# proximity_kt.net
KiCad netlist of a schematic drawn in Altium Designer
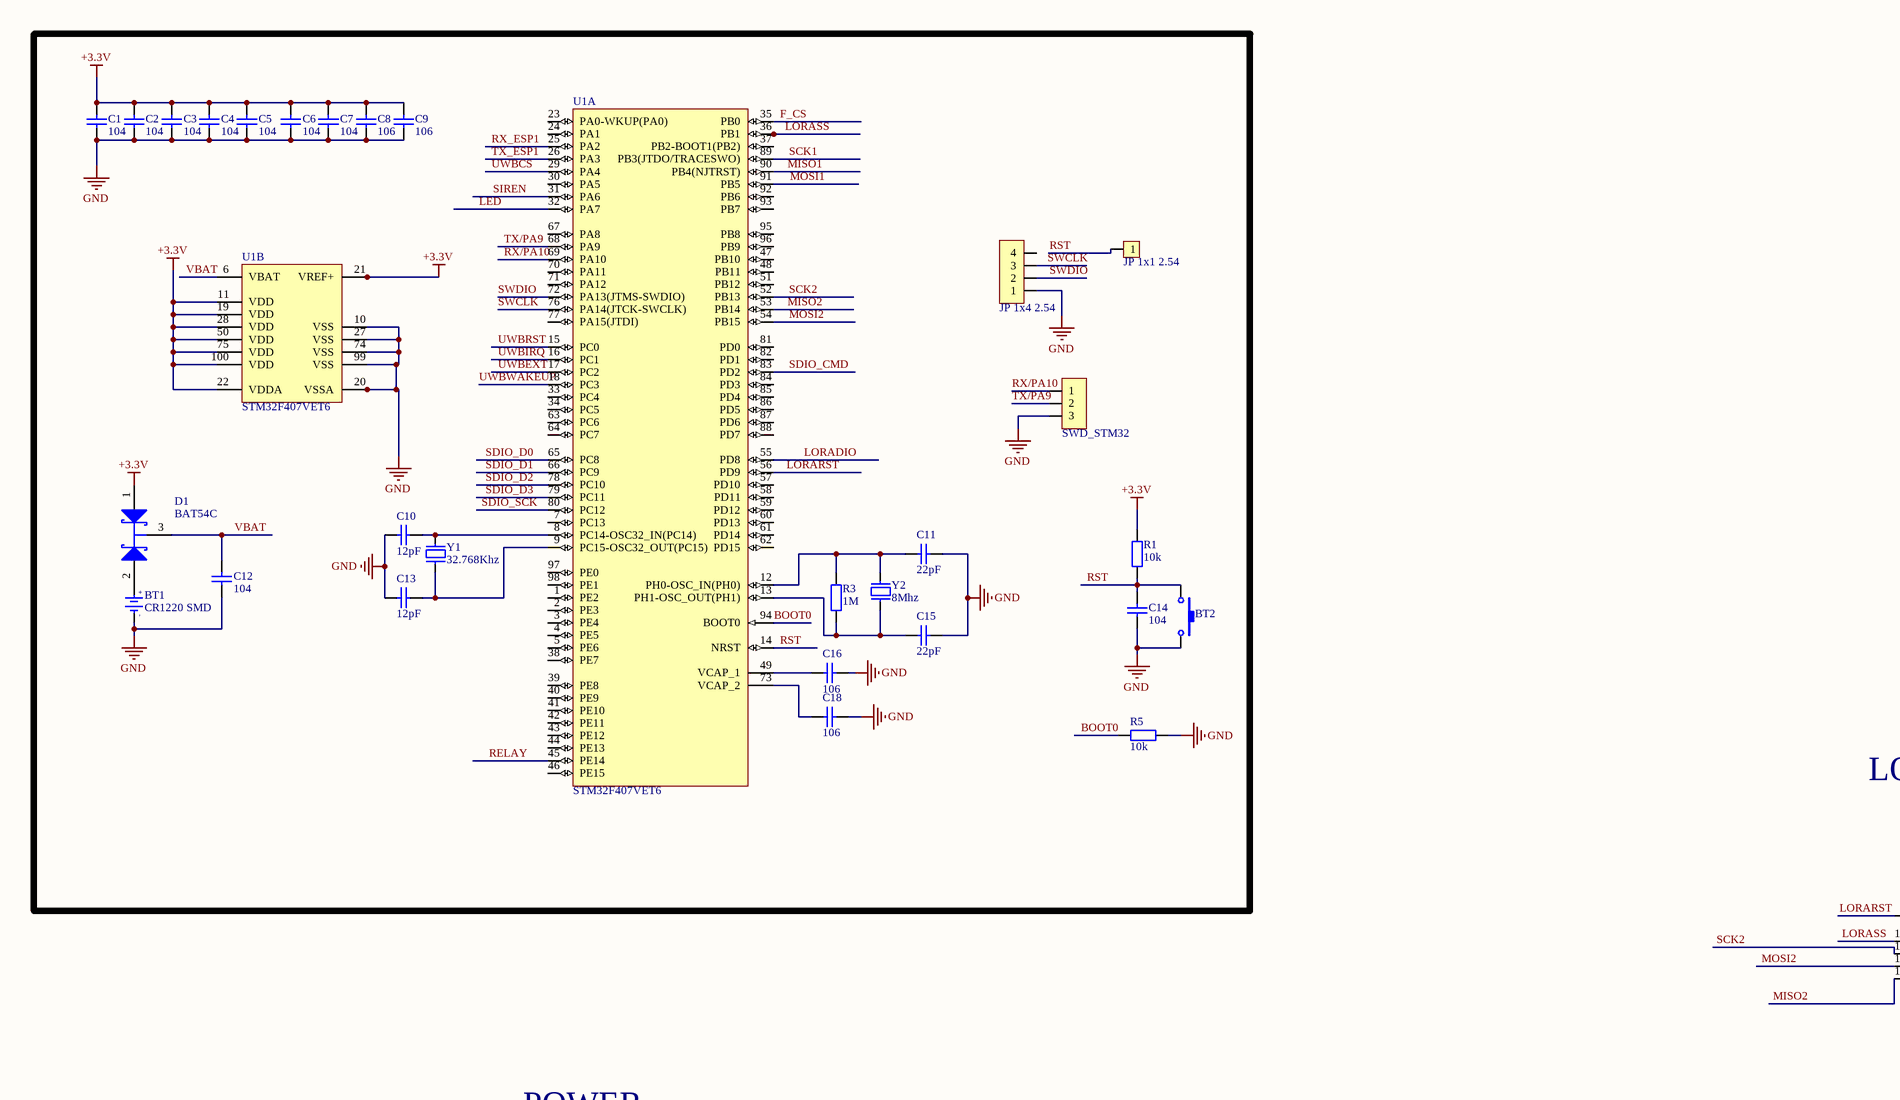
[diagram p0: proximity_kt.SchDoc, top left]
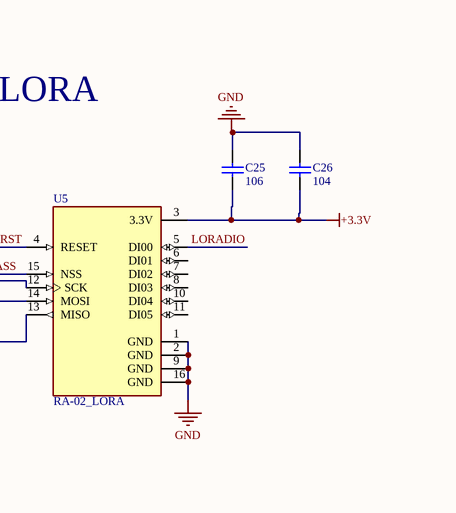
[diagram p1: proximity_kt.SchDoc, top right]
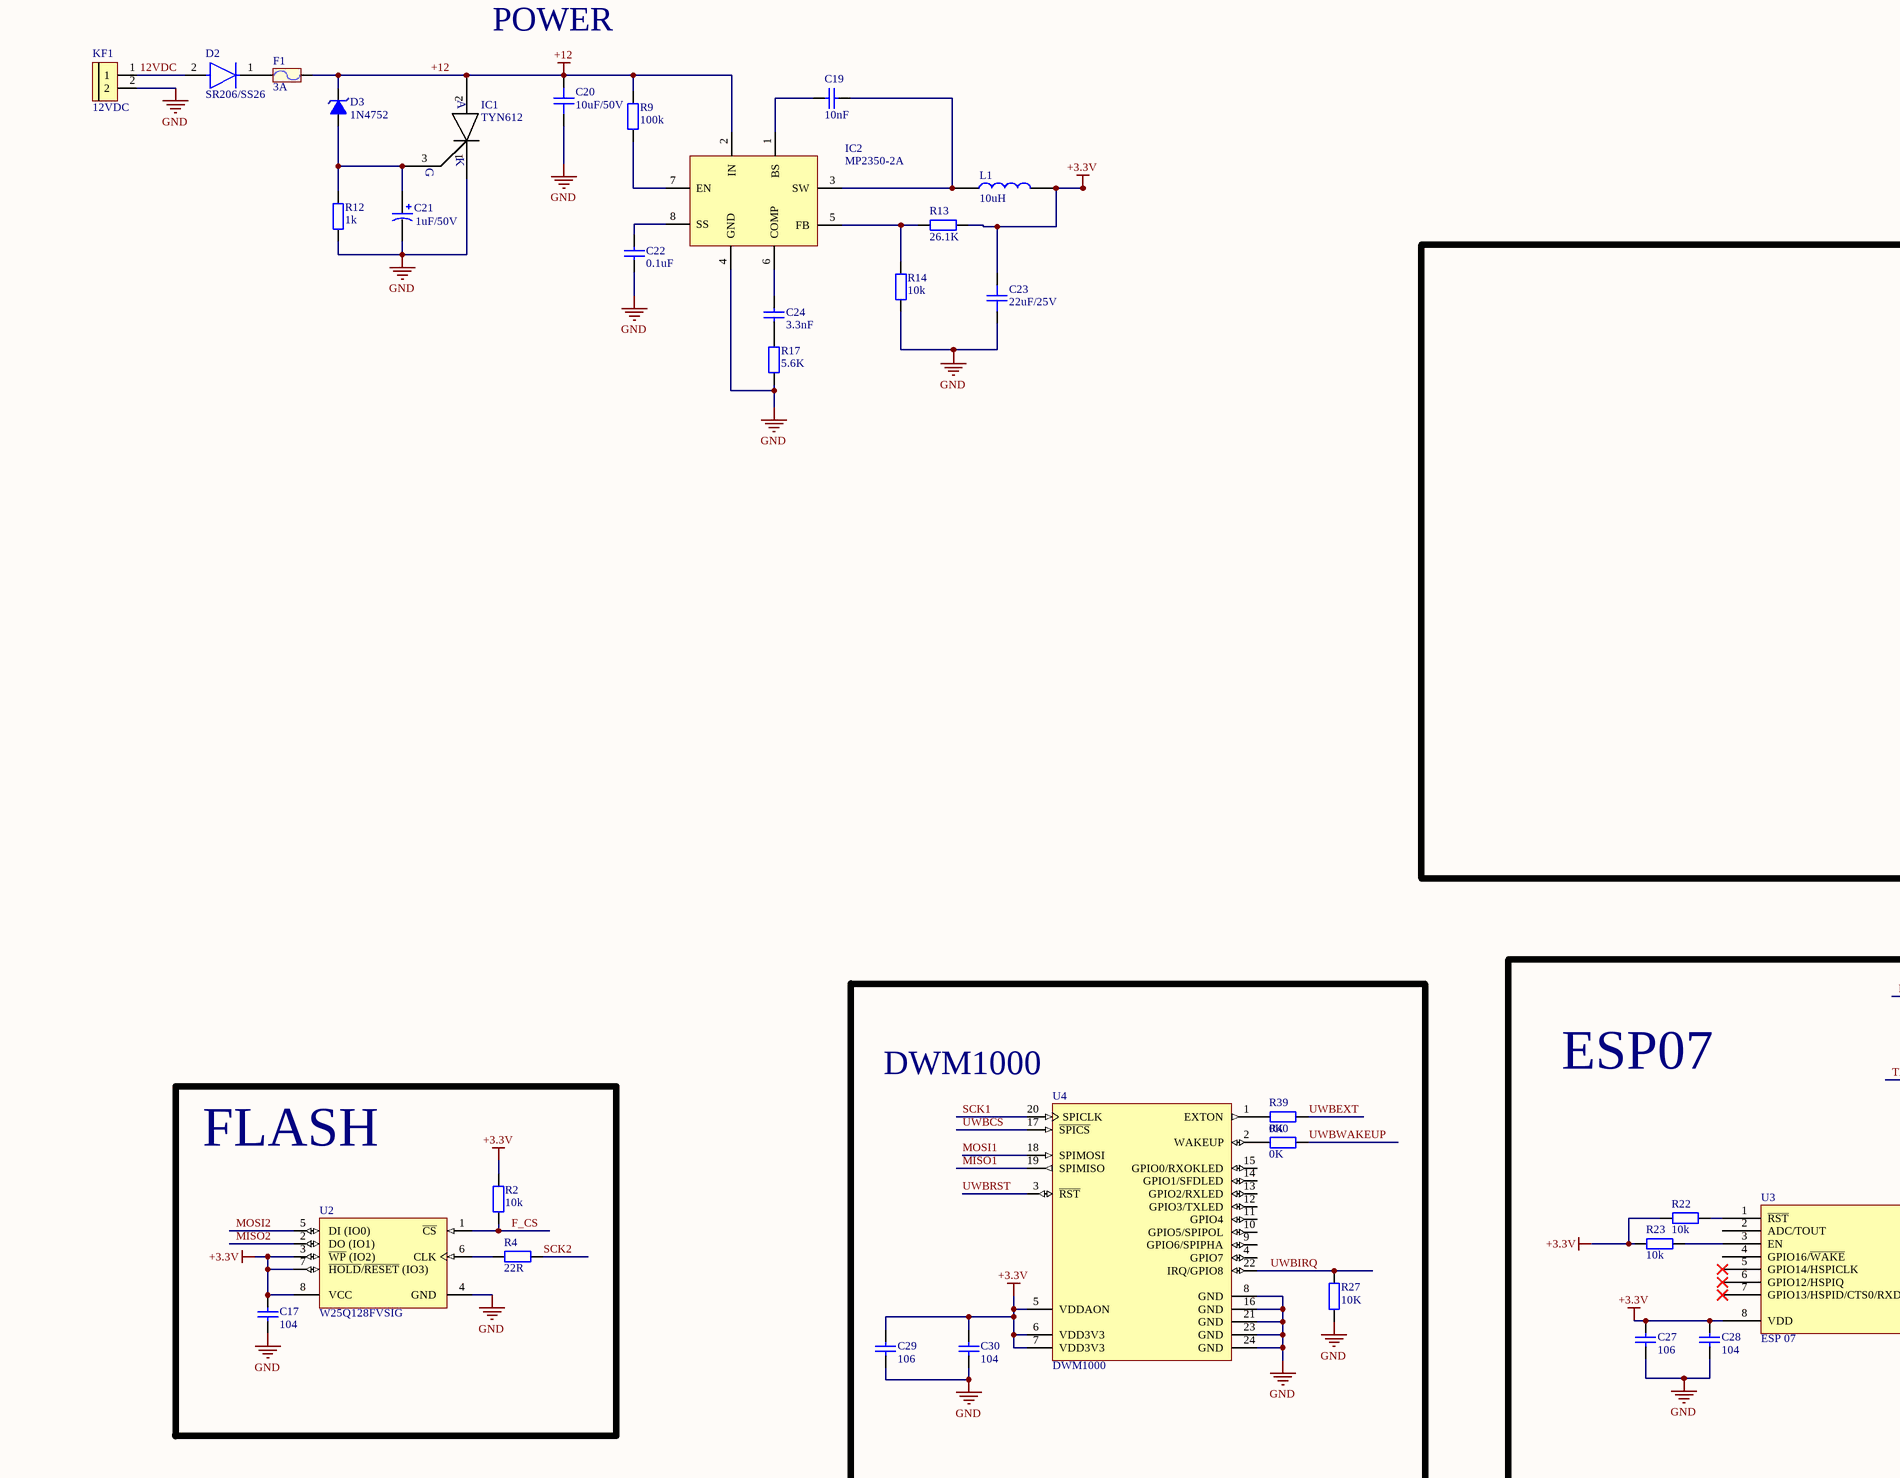
[diagram p2: proximity_kt.SchDoc, bottom left]
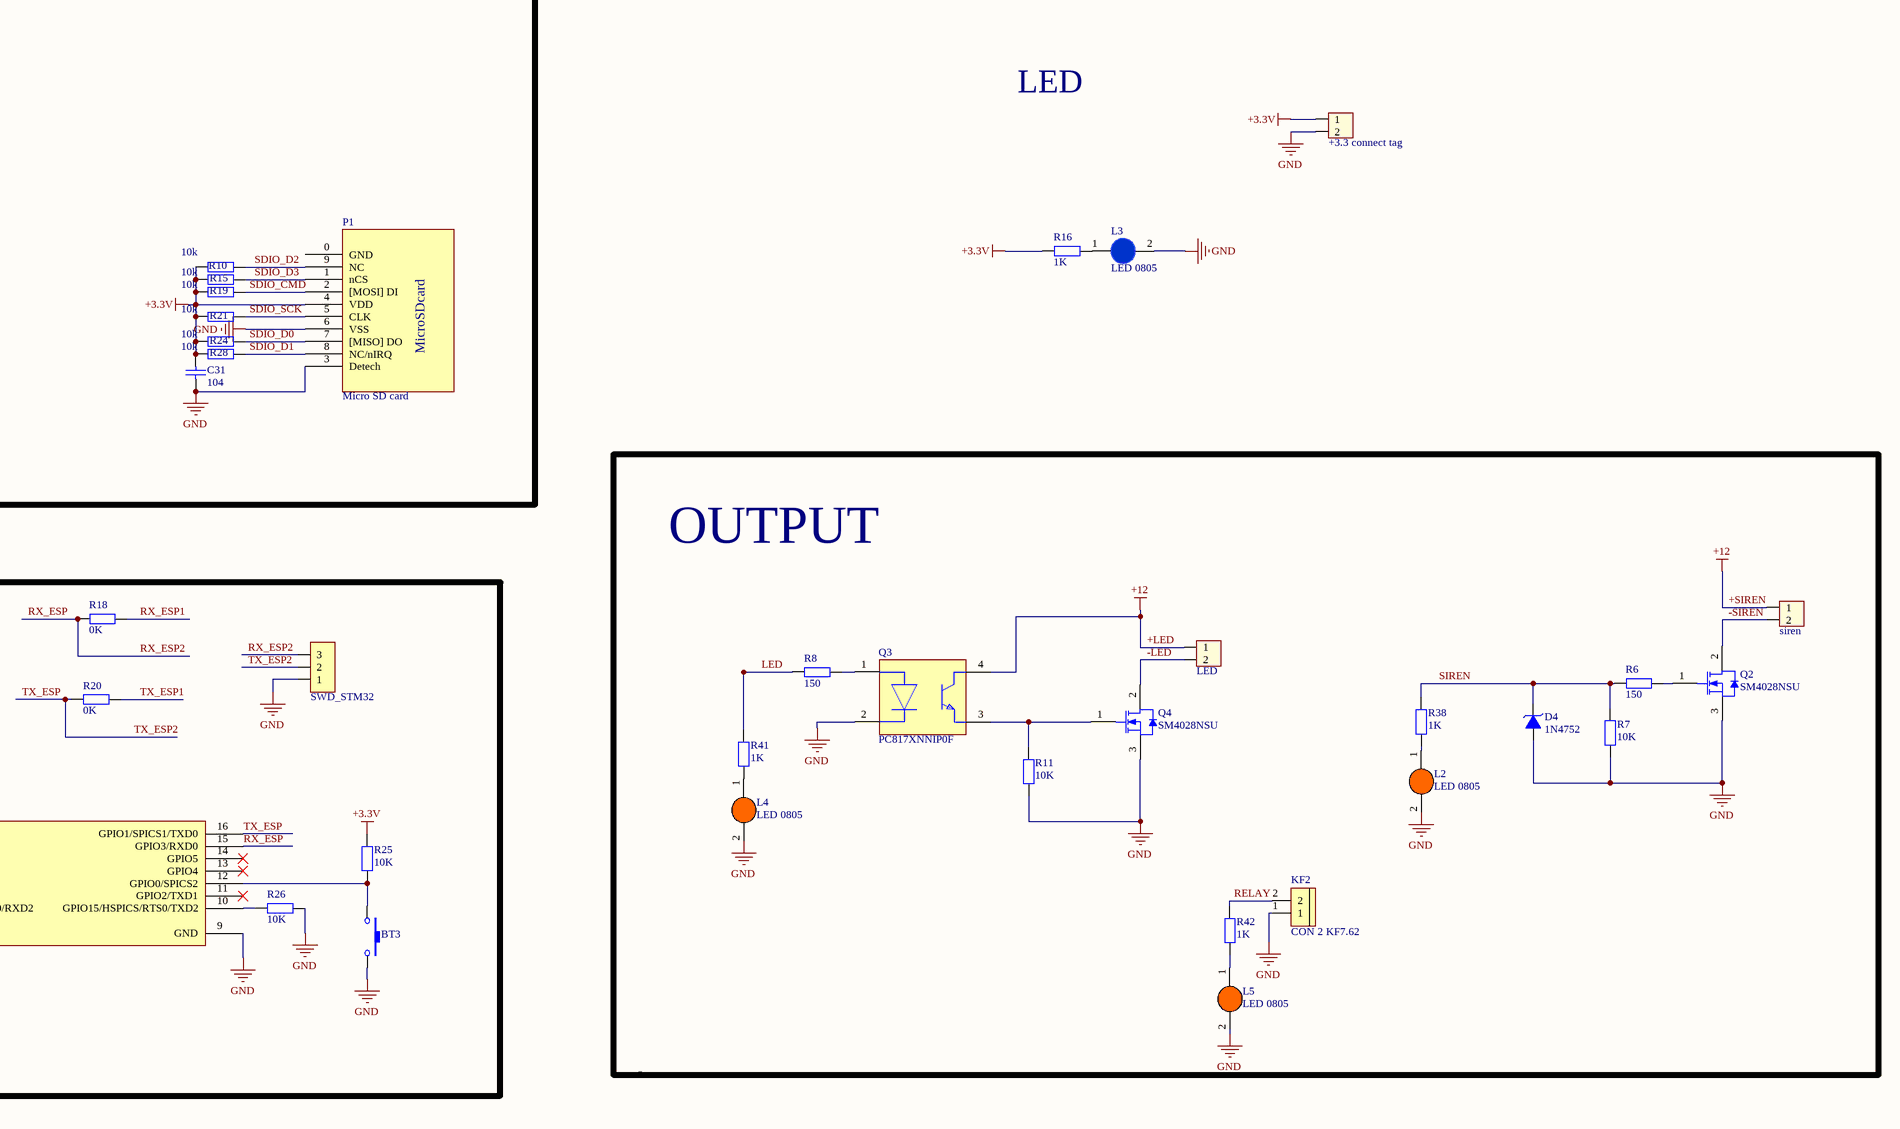
[diagram p3: proximity_kt.SchDoc, bottom right]

(export (version "E")
  (design (tool "Eeschema 10.0.6"))
  (components
    (comp (ref "BT1")
      (value "CR1220 SMD")
      (footprint "DE PIN CR1220")
      (libsource (lib "Altium_Lib_by_KhueNguyenCreator") (part "De pin CR1220 SMD"))
    )
    (comp (ref "BT2")
      (value "Nut Nhan 2 Chan SMD 3x6x2.5")
      (footprint "Nut Nhan 2 Chan SMD 3x6x2.5")
      (libsource (lib "Altium_Lib_by_KhueNguyenCreator") (part "Nut Nhan 2 Chan SMD 3x6x2.5"))
    )
    (comp (ref "BT3")
      (value "Nut Nhan 2 Chan SMD 3x6x2.5")
      (footprint "Nut Nhan 2 Chan SMD 3x6x2.5")
      (libsource (lib "Altium_Lib_by_KhueNguyenCreator") (part "Nut Nhan 2 Chan SMD 3x6x2.5"))
    )
    (comp (ref "C1")
      (value "104")
      (footprint "tu 0805")
      (description "Dán")
      (libsource (lib "Altium_Lib_by_KhueNguyenCreator") (part "Tu 0805 104 50V 10%"))
    )
    (comp (ref "C2")
      (value "104")
      (footprint "tu 0805")
      (description "Dán")
      (libsource (lib "Altium_Lib_by_KhueNguyenCreator") (part "Tu 0805 104 50V 10%"))
    )
    (comp (ref "C3")
      (value "104")
      (footprint "tu 0805")
      (description "Dán")
      (libsource (lib "Altium_Lib_by_KhueNguyenCreator") (part "Tu 0805 104 50V 10%"))
    )
    (comp (ref "C4")
      (value "104")
      (footprint "tu 0805")
      (description "Dán")
      (libsource (lib "Altium_Lib_by_KhueNguyenCreator") (part "Tu 0805 104 50V 10%"))
    )
    (comp (ref "C5")
      (value "104")
      (footprint "tu 0805")
      (description "Dán")
      (libsource (lib "Altium_Lib_by_KhueNguyenCreator") (part "Tu 0805 104 50V 10%"))
    )
    (comp (ref "C6")
      (value "104")
      (footprint "tu 0805")
      (description "Dán")
      (libsource (lib "Altium_Lib_by_KhueNguyenCreator") (part "Tu 0805 104 50V 10%"))
    )
    (comp (ref "C7")
      (value "104")
      (footprint "tu 0805")
      (description "Dán")
      (libsource (lib "Altium_Lib_by_KhueNguyenCreator") (part "Tu 0805 104 50V 10%"))
    )
    (comp (ref "C8")
      (value "106")
      (footprint "tu 0805")
      (description "Dán")
      (libsource (lib "Altium_Lib_by_KhueNguyenCreator") (part "Tu 0805 106 16V 10%"))
    )
    (comp (ref "C9")
      (value "106")
      (footprint "tu 0805")
      (description "Dán")
      (libsource (lib "Altium_Lib_by_KhueNguyenCreator") (part "Tu 0805 106 16V 10%"))
    )
    (comp (ref "C10")
      (value "12pF")
      (footprint "tu 0805")
      (description "Dán")
      (libsource (lib "Altium_Lib_by_KhueNguyenCreator") (part "Tu 0805 15pF 50V 10%"))
    )
    (comp (ref "C11")
      (value "22pF")
      (footprint "tu 0805")
      (description "Dán")
      (libsource (lib "Altium_Lib_by_KhueNguyenCreator") (part "Tu 0805 22pF 50V 10%"))
    )
    (comp (ref "C12")
      (value "104")
      (footprint "tu 0805")
      (description "Dán")
      (libsource (lib "Altium_Lib_by_KhueNguyenCreator") (part "Tu 0805 104 50V 10%"))
    )
    (comp (ref "C13")
      (value "12pF")
      (footprint "tu 0805")
      (description "Dán")
      (libsource (lib "Altium_Lib_by_KhueNguyenCreator") (part "Tu 0805 15pF 50V 10%"))
    )
    (comp (ref "C14")
      (value "104")
      (footprint "tu 0805")
      (description "Dán")
      (libsource (lib "Altium_Lib_by_KhueNguyenCreator") (part "Tu 0805 104 50V 10%"))
    )
    (comp (ref "C15")
      (value "22pF")
      (footprint "tu 0805")
      (description "Dán")
      (libsource (lib "Altium_Lib_by_KhueNguyenCreator") (part "Tu 0805 22pF 50V 10%"))
    )
    (comp (ref "C16")
      (value "106")
      (footprint "tu 0805")
      (description "Dán")
      (libsource (lib "Altium_Lib_by_KhueNguyenCreator") (part "Tu 0805 106 16V 10%"))
    )
    (comp (ref "C17")
      (value "104")
      (footprint "tu 0805")
      (description "Dán")
      (libsource (lib "Altium_Lib_by_KhueNguyenCreator") (part "Tu 0805 104 50V 10%"))
    )
    (comp (ref "C18")
      (value "106")
      (footprint "tu 0805")
      (description "Dán")
      (libsource (lib "Altium_Lib_by_KhueNguyenCreator") (part "Tu 0805 106 16V 10%"))
    )
    (comp (ref "C19")
      (value "10nF")
      (footprint "tu 0805")
      (description "Dán")
      (libsource (lib "Altium_Lib_by_KhueNguyenCreator") (part "Tu 0805 104 50V 10%"))
    )
    (comp (ref "C20")
      (value "10uF/50V")
      (footprint "CAPC-1210 (3225)")
      (description "CAP CER 220uF 20% 6.3V X5R 1210")
      (fields (field (name "MPN") "CL32A227MQVNNNE"))
      (libsource (lib "BYTECH_HW_LIB_2019 ") (part "CL32A227MQVNNNE"))
    )
    (comp (ref "C21")
      (value "1uF/50V")
      (footprint "CAP_ALUM_SMD_4054_TYPE_B")
      (description "CAP ALUM 10uF 20% 16V SMD")
      (fields (field (name "MPN") "EEE-HA1C100P") (field (name "MFR") "Panasonic"))
      (libsource (lib "BYTECH_HW_LIB_2019 ") (part "EEE-HA1C100P"))
    )
    (comp (ref "C22")
      (value "0.1uF")
      (footprint "tu 0805")
      (description "Dán")
      (libsource (lib "Altium_Lib_by_KhueNguyenCreator") (part "Tu 0805 104 50V 10%"))
    )
    (comp (ref "C23")
      (value "22uF/25V")
      (footprint "CAPC-1210 (3225)")
      (description "CAP CER 220uF 20% 6.3V X5R 1210")
      (fields (field (name "MPN") "CL32A227MQVNNNE"))
      (libsource (lib "BYTECH_HW_LIB_2019 ") (part "CL32A227MQVNNNE"))
    )
    (comp (ref "C24")
      (value "3.3nF")
      (footprint "tu 0805")
      (description "Dán")
      (libsource (lib "Altium_Lib_by_KhueNguyenCreator") (part "Tu 0805 104 50V 10%"))
    )
    (comp (ref "C25")
      (value "106")
      (footprint "tu 0805")
      (description "Dán")
      (libsource (lib "Altium_Lib_by_KhueNguyenCreator") (part "Tu 0805 106 16V 10%"))
    )
    (comp (ref "C26")
      (value "104")
      (footprint "tu 0805")
      (description "Dán")
      (libsource (lib "Altium_Lib_by_KhueNguyenCreator") (part "Tu 0805 104 50V 10%"))
    )
    (comp (ref "C27")
      (value "106")
      (footprint "tu 0805")
      (description "Dán")
      (libsource (lib "Altium_Lib_by_KhueNguyenCreator") (part "Tu 0805 106 16V 10%"))
    )
    (comp (ref "C28")
      (value "104")
      (footprint "tu 0805")
      (description "Dán")
      (libsource (lib "Altium_Lib_by_KhueNguyenCreator") (part "Tu 0805 104 50V 10%"))
    )
    (comp (ref "C29")
      (value "106")
      (footprint "tu 0805")
      (description "Dán")
      (libsource (lib "Altium_Lib_by_KhueNguyenCreator") (part "Tu 0805 106 16V 10%"))
    )
    (comp (ref "C30")
      (value "104")
      (footprint "tu 0805")
      (description "Dán")
      (libsource (lib "Altium_Lib_by_KhueNguyenCreator") (part "Tu 0805 104 50V 10%"))
    )
    (comp (ref "C31")
      (value "104")
      (footprint "tu 0805")
      (description "Dán")
      (libsource (lib "Altium_Lib_by_KhueNguyenCreator") (part "Tu 0805 104 50V 10%"))
    )
    (comp (ref "D1")
      (value "BAT54C")
      (footprint "NXP-SOT23-3_V")
      (description "Schottky Barrier Diode, 30 V, 2 uA, -55 to 150 degC, 3-Pin SOT23, RoHS, Tape and Reel")
      (fields (field (name "MANUFACTURER") "NXP Semiconductors"))
      (libsource (lib "Altium Content Vault") (part "NXP-DSKY_A1A2K3-3"))
    )
    (comp (ref "D2")
      (value "SR206/SS26")
      (footprint "FP-95401-MFG")
      (description "DIODE GEN PURP 600V 2A DO214AA")
      (libsource (lib "Altium Content Vault") (part "d7152d700b627762746794eb795d46e"))
    )
    (comp (ref "D3")
      (value "1N4752")
      (footprint "DIODE ZENNER SMD SOD80")
      (description "Dán")
      (libsource (lib "Altium_Lib_by_KhueNguyenCreator") (part "Diode Zener 15V"))
    )
    (comp (ref "D4")
      (value "1N4752")
      (footprint "DIODE ZENNER SMD SOD80")
      (description "Dán")
      (libsource (lib "Altium_Lib_by_KhueNguyenCreator") (part "Diode Zener 15V"))
    )
    (comp (ref "F1")
      (value "3A")
      (footprint "Cau Chi SMD1808")
      (description "Cau chi 0.5A 125V SMD1808")
      (libsource (lib "Altium_Lib_by_KhueNguyenCreator") (part "Cau chi 0.5A 125V SMD1808"))
    )
    (comp (ref "H2")
      (value "siren")
      (footprint "XH2.54M-2")
      (description "Cắm")
      (libsource (lib "Altium_Lib_by_KhueNguyenCreator") (part "Header 2P 2.54 Duc Thang"))
    )
    (comp (ref "H3")
      (value "+3.3 connect tag")
      (footprint "XH2.54M-2")
      (description "Cắm")
      (libsource (lib "Altium_Lib_by_KhueNguyenCreator") (part "Header 2P 2.54 Duc Thang"))
    )
    (comp (ref "H5")
      (value "LED")
      (footprint "XH2.54M-2")
      (description "Cắm")
      (libsource (lib "Altium_Lib_by_KhueNguyenCreator") (part "Header 2P 2.54 Duc Thang"))
    )
    (comp (ref "IC1")
      (value "TYN612")
      (footprint "TYN612VER1")
      (libsource (lib "Integrated_Library1") (part "TYN612"))
    )
    (comp (ref "IC2")
      (value "MP2350-2A")
      (footprint "MP2305")
      (libsource (lib "Integrated_Library1") (part "MP2350-2A"))
    )
    (comp (ref "JP1")
      (value "JP 1x4 2.54")
      (footprint "JP 1x4 DT")
      (description "Cắm")
      (libsource (lib "Altium_Lib_by_KhueNguyenCreator") (part "JP 1x4 2.54 Duc Thang"))
    )
    (comp (ref "JP2")
      (value "SWD_STM32")
      (footprint "JP 1x3 DT")
      (description "Cắm")
      (libsource (lib "Altium_Lib_by_KhueNguyenCreator") (part "JP 1x3 2.54 Duc Thang"))
    )
    (comp (ref "JP3")
      (value "SWD_STM32")
      (footprint "JP 1x3 DT")
      (description "Cắm")
      (libsource (lib "") (part "JP 1x3 2.54 Duc Thang_1"))
    )
    (comp (ref "JP5")
      (value "JP 1x1 2.54")
      (footprint "JP 1x1 DT")
      (description "Cắm")
      (libsource (lib "Altium_Lib_by_KhueNguyenCreator") (part "JP 1x1 2.54 Duc Thang"))
    )
    (comp (ref "KF1")
      (value "12VDC")
      (footprint "Con 2 KF301 5.08")
      (description "Cắm")
      (libsource (lib "Altium_Lib_by_KhueNguyenCreator") (part "CON 2 KF301"))
    )
    (comp (ref "KF2")
      (value "CON 2 KF7.62")
      (footprint "CON 2 KF7.62")
      (description "Cắm")
      (libsource (lib "Altium_Lib_by_KhueNguyenCreator") (part "CON 2 KF7.62"))
    )
    (comp (ref "L1")
      (value "10uH")
      (footprint "Cuon Cam 7x7x5")
      (description "Dán")
      (libsource (lib "Altium_Lib_by_KhueNguyenCreator") (part "CUON CAM 47uH SMD"))
    )
    (comp (ref "L2")
      (value "LED 0805")
      (footprint "LED-0805-Orange")
      (description "Dán")
      (libsource (lib "Altium_Lib_by_KhueNguyenCreator") (part "LED 0805 Cam"))
    )
    (comp (ref "L3")
      (value "LED 0805")
      (footprint "LED-0805-Blue")
      (description "Dán")
      (libsource (lib "Altium_Lib_by_KhueNguyenCreator") (part "LED 0805 Xanh Duong"))
    )
    (comp (ref "L4")
      (value "LED 0805")
      (footprint "LED-0805-Orange")
      (description "Dán")
      (libsource (lib "Altium_Lib_by_KhueNguyenCreator") (part "LED 0805 Cam"))
    )
    (comp (ref "L5")
      (value "LED 0805")
      (footprint "LED-0805-Orange")
      (description "Dán")
      (libsource (lib "Altium_Lib_by_KhueNguyenCreator") (part "LED 0805 Cam"))
    )
    (comp (ref "P1")
      (value "Micro SD card")
      (footprint "MicroSD")
      (libsource (lib "Altium_Lib_by_KhueNguyenCreator") (part "Micro SD card"))
    )
    (comp (ref "Q2")
      (value "SM4028NSU")
      (footprint "INF-PG-TO252-3-313_L")
      (fields (field (name "MANUFACTURER") "Infineon") (field (name "PARTNUMBER") "IPD60R600C6"))
      (libsource (lib "Altium Content Vault") (part "INF-NEMOS-GDS-3"))
    )
    (comp (ref "Q3")
      (value "PC817XNNIP0F")
      (footprint "FP-PC817XNNIP0F-MFG")
      (description "OPTOISOLATOR 5KV TRANS 4SMD")
      (libsource (lib "Altium Content Vault") (part "6470904bf6395c62928ee73e60120b8"))
    )
    (comp (ref "Q4")
      (value "SM4028NSU")
      (footprint "INF-PG-TO252-3-313_L")
      (fields (field (name "MANUFACTURER") "Infineon") (field (name "PARTNUMBER") "IPD60R600C6"))
      (libsource (lib "Altium Content Vault") (part "INF-NEMOS-GDS-3"))
    )
    (comp (ref "R1")
      (value "10k")
      (footprint "tro smd 0805")
      (description "Dán")
      (libsource (lib "Altium_Lib_by_KhueNguyenCreator") (part "Tro 0805 5% 10k"))
    )
    (comp (ref "R2")
      (value "10k")
      (footprint "tro smd 0805")
      (description "Dán")
      (libsource (lib "Altium_Lib_by_KhueNguyenCreator") (part "Tro 0805 5% 10k"))
    )
    (comp (ref "R3")
      (value "1M")
      (footprint "tro smd 0805")
      (description "Dán")
      (libsource (lib "Altium_Lib_by_KhueNguyenCreator") (part "Tro 0805 1% 1M"))
    )
    (comp (ref "R4")
      (value "22R")
      (footprint "tro smd 0805")
      (description "Dán")
      (libsource (lib "Altium_Lib_by_KhueNguyenCreator") (part "Tro 0805 1% 0.22R"))
    )
    (comp (ref "R5")
      (value "10k")
      (footprint "tro smd 0805")
      (description "Dán")
      (libsource (lib "Altium_Lib_by_KhueNguyenCreator") (part "Tro 0805 5% 10k"))
    )
    (comp (ref "R6")
      (value "150")
      (footprint "tro smd 0805")
      (description "Dán")
      (libsource (lib "Altium_Lib_by_KhueNguyenCreator") (part "Tro 0603 5% 10k"))
    )
    (comp (ref "R7")
      (value "10K")
      (footprint "tro smd 0805")
      (description "Dán")
      (libsource (lib "Altium_Lib_by_KhueNguyenCreator") (part "Tro 0603 5% 10k"))
    )
    (comp (ref "R8")
      (value "150")
      (footprint "tro smd 0805")
      (description "Dán")
      (libsource (lib "Altium_Lib_by_KhueNguyenCreator") (part "Tro 0603 5% 10k"))
    )
    (comp (ref "R9")
      (value "100k")
      (footprint "tro smd 0805")
      (description "Dán")
      (libsource (lib "Altium_Lib_by_KhueNguyenCreator") (part "Tro 0805 5% 10k"))
    )
    (comp (ref "R10")
      (value "10k")
      (footprint "tro smd 0805")
      (description "Dán")
      (libsource (lib "Altium_Lib_by_KhueNguyenCreator") (part "Tro 0805 5% 10k"))
    )
    (comp (ref "R11")
      (value "10K")
      (footprint "tro smd 0805")
      (description "Dán")
      (libsource (lib "Altium_Lib_by_KhueNguyenCreator") (part "Tro 0603 5% 10k"))
    )
    (comp (ref "R12")
      (value "1k")
      (footprint "tro smd 0805")
      (description "Dán")
      (libsource (lib "Altium_Lib_by_KhueNguyenCreator") (part "Tro 0805 1% 1k"))
    )
    (comp (ref "R13")
      (value "26.1K")
      (footprint "tro smd 0805")
      (description "Dán")
      (libsource (lib "Altium_Lib_by_KhueNguyenCreator") (part "Tro 0805 5% 10k"))
    )
    (comp (ref "R14")
      (value "10k")
      (footprint "tro smd 0805")
      (description "Dán")
      (libsource (lib "Altium_Lib_by_KhueNguyenCreator") (part "Tro 0805 5% 10k"))
    )
    (comp (ref "R15")
      (value "10k")
      (footprint "tro smd 0805")
      (description "Dán")
      (libsource (lib "Altium_Lib_by_KhueNguyenCreator") (part "Tro 0805 5% 10k"))
    )
    (comp (ref "R16")
      (value "1K")
      (footprint "tro smd 0805")
      (description "Dán")
      (libsource (lib "Altium_Lib_by_KhueNguyenCreator") (part "Tro 0603 5% 10k"))
    )
    (comp (ref "R17")
      (value "5.6K")
      (footprint "tro smd 0805")
      (description "Dán")
      (libsource (lib "Altium_Lib_by_KhueNguyenCreator") (part "Tro 0805 5% 10k"))
    )
    (comp (ref "R18")
      (value "0K")
      (footprint "tro smd 0805")
      (description "Dán")
      (libsource (lib "Altium_Lib_by_KhueNguyenCreator") (part "Tro 0603 5% 10k"))
    )
    (comp (ref "R19")
      (value "10k")
      (footprint "tro smd 0805")
      (description "Dán")
      (libsource (lib "Altium_Lib_by_KhueNguyenCreator") (part "Tro 0805 5% 10k"))
    )
    (comp (ref "R20")
      (value "0K")
      (footprint "tro smd 0805")
      (description "Dán")
      (libsource (lib "Altium_Lib_by_KhueNguyenCreator") (part "Tro 0603 5% 10k"))
    )
    (comp (ref "R21")
      (value "10k")
      (footprint "tro smd 0805")
      (description "Dán")
      (libsource (lib "Altium_Lib_by_KhueNguyenCreator") (part "Tro 0805 5% 10k"))
    )
    (comp (ref "R22")
      (value "10k")
      (footprint "tro smd 0805")
      (description "Dán")
      (libsource (lib "Altium_Lib_by_KhueNguyenCreator") (part "Tro 0805 5% 10k"))
    )
    (comp (ref "R23")
      (value "10k")
      (footprint "tro smd 0805")
      (description "Dán")
      (libsource (lib "Altium_Lib_by_KhueNguyenCreator") (part "Tro 0805 5% 10k"))
    )
    (comp (ref "R24")
      (value "10k")
      (footprint "tro smd 0805")
      (description "Dán")
      (libsource (lib "Altium_Lib_by_KhueNguyenCreator") (part "Tro 0805 5% 10k"))
    )
    (comp (ref "R25")
      (value "10K")
      (footprint "tro smd 0805")
      (description "Dán")
      (libsource (lib "Altium_Lib_by_KhueNguyenCreator") (part "Tro 0603 5% 10k"))
    )
    (comp (ref "R26")
      (value "10K")
      (footprint "tro smd 0805")
      (description "Dán")
      (libsource (lib "Altium_Lib_by_KhueNguyenCreator") (part "Tro 0603 5% 10k"))
    )
    (comp (ref "R27")
      (value "10K")
      (footprint "tro smd 0805")
      (description "Dán")
      (libsource (lib "Altium_Lib_by_KhueNguyenCreator") (part "Tro 0603 5% 10k"))
    )
    (comp (ref "R28")
      (value "10k")
      (footprint "tro smd 0805")
      (description "Dán")
      (libsource (lib "Altium_Lib_by_KhueNguyenCreator") (part "Tro 0805 5% 10k"))
    )
    (comp (ref "R38")
      (value "1K")
      (footprint "tro smd 0805")
      (description "Dán")
      (libsource (lib "Altium_Lib_by_KhueNguyenCreator") (part "Tro 0603 5% 10k"))
    )
    (comp (ref "R39")
      (value "0K")
      (footprint "tro smd 0805")
      (description "Dán")
      (libsource (lib "Altium_Lib_by_KhueNguyenCreator") (part "Tro 0603 5% 10k"))
    )
    (comp (ref "R40")
      (value "0K")
      (footprint "tro smd 0805")
      (description "Dán")
      (libsource (lib "Altium_Lib_by_KhueNguyenCreator") (part "Tro 0603 5% 10k"))
    )
    (comp (ref "R41")
      (value "1K")
      (footprint "tro smd 0805")
      (description "Dán")
      (libsource (lib "Altium_Lib_by_KhueNguyenCreator") (part "Tro 0603 5% 10k"))
    )
    (comp (ref "R42")
      (value "1K")
      (footprint "tro smd 0805")
      (description "Dán")
      (libsource (lib "Altium_Lib_by_KhueNguyenCreator") (part "Tro 0603 5% 10k"))
    )
    (comp (ref "U1")
      (value "STM32F407VET6")
      (footprint "STM-LQFP100_M")
      (fields (field (name "MANUFACTURER") "STMicroelectronics"))
      (libsource (lib "Altium Content Vault") (part "MC-ARM-STM32F40X_41X-SQ100"))
    )
    (comp (ref "U2")
      (value "W25Q128FVSIG")
      (footprint "WINB-SOIC-8_M")
      (fields (field (name "MANUFACTURER") "Winbond"))
      (libsource (lib "Altium Content Vault") (part "WINB-W25Q128FVSIG-SOIC-8"))
    )
    (comp (ref "U3")
      (value "ESP 07")
      (footprint "ESP8266 07")
      (description "ESP8266 07 16 Pin")
      (libsource (lib "Altium_Lib_by_KhueNguyenCreator") (part "ESP8266 07"))
    )
    (comp (ref "U4")
      (value "DWM1000")
      (footprint "DECW-DWM1000-24_V")
      (description "DW M1000 IEEE 802.15.4 -2011 UWB Transceiver Module")
      (fields (field (name "MANUFACTURER") "Decawave"))
      (libsource (lib "Altium Content Vault") (part "DECW-DWM1000-24"))
    )
    (comp (ref "U5")
      (value "RA-02_LORA")
      (footprint "MODULE_RA-02_LORA")
      (description "Ra-02 LoRa RF M5Stack Platform Evaluation Expansion Board")
      (fields (field (name "MP") "Ra-02 LoRa") (field (name "MF") "AI-Thinker"))
      (libsource (lib "Integrated_Library1") (part "RA-02_LORA"))
    )
    (comp (ref "Y1")
      (value "32.768Khz")
      (footprint "Thach Anh 2 Chan 32,768 KHz")
      (description "Crystal For all Crystal 2pin.")
      (libsource (lib "Altium_Lib_by_KhueNguyenCreator") (part "Thach Anh 2 chan 32,768 Khz"))
    )
    (comp (ref "Y2")
      (value "8Mhz")
      (footprint "Thach Anh 2 chan SMD")
      (description "Crystal For all Crystal 2pin.")
      (libsource (lib "Altium_Lib_by_KhueNguyenCreator") (part "Thach Anh 2 chan SMD"))
    )
  )
  (nets
    (net (code "1") (name "+3.3V") (class "Default")
      (node (ref "C1") (pin "1") (pinfunction "1_1") (pintype "passive"))
      (node (ref "C17") (pin "1") (pinfunction "1_1") (pintype "passive"))
      (node (ref "C2") (pin "1") (pinfunction "1_1") (pintype "passive"))
      (node (ref "C23") (pin "2") (pinfunction "2_2") (pintype "passive"))
      (node (ref "C25") (pin "2") (pinfunction "2_2") (pintype "passive"))
      (node (ref "C26") (pin "2") (pinfunction "2_2") (pintype "passive"))
      (node (ref "C27") (pin "1") (pinfunction "1_1") (pintype "passive"))
      (node (ref "C28") (pin "1") (pinfunction "1_1") (pintype "passive"))
      (node (ref "C29") (pin "1") (pinfunction "1_1") (pintype "passive"))
      (node (ref "C3") (pin "1") (pinfunction "1_1") (pintype "passive"))
      (node (ref "C30") (pin "1") (pinfunction "1_1") (pintype "passive"))
      (node (ref "C31") (pin "1") (pinfunction "1_1") (pintype "passive"))
      (node (ref "C4") (pin "1") (pinfunction "1_1") (pintype "passive"))
      (node (ref "C5") (pin "1") (pinfunction "1_1") (pintype "passive"))
      (node (ref "C6") (pin "1") (pinfunction "1_1") (pintype "passive"))
      (node (ref "C7") (pin "1") (pinfunction "1_1") (pintype "passive"))
      (node (ref "C8") (pin "1") (pinfunction "1_1") (pintype "passive"))
      (node (ref "C9") (pin "1") (pinfunction "1_1") (pintype "passive"))
      (node (ref "D1") (pin "1") (pinfunction "A_1") (pintype "passive"))
      (node (ref "H3") (pin "1") (pinfunction "1_1") (pintype "passive"))
      (node (ref "L1") (pin "2") (pinfunction "2_2") (pintype "passive"))
      (node (ref "P1") (pin "4") (pinfunction "VDD_4") (pintype "passive"))
      (node (ref "R1") (pin "2") (pinfunction "2_2") (pintype "passive"))
      (node (ref "R10") (pin "2") (pinfunction "2_2") (pintype "passive"))
      (node (ref "R13") (pin "2") (pinfunction "2_2") (pintype "passive"))
      (node (ref "R15") (pin "2") (pinfunction "2_2") (pintype "passive"))
      (node (ref "R16") (pin "2") (pinfunction "2_2") (pintype "passive"))
      (node (ref "R19") (pin "2") (pinfunction "2_2") (pintype "passive"))
      (node (ref "R2") (pin "2") (pinfunction "2_2") (pintype "passive"))
      (node (ref "R21") (pin "2") (pinfunction "2_2") (pintype "passive"))
      (node (ref "R22") (pin "2") (pinfunction "2_2") (pintype "passive"))
      (node (ref "R23") (pin "2") (pinfunction "2_2") (pintype "passive"))
      (node (ref "R24") (pin "2") (pinfunction "2_2") (pintype "passive"))
      (node (ref "R25") (pin "2") (pinfunction "2_2") (pintype "passive"))
      (node (ref "R28") (pin "2") (pinfunction "2_2") (pintype "passive"))
      (node (ref "U1") (pin "100") (pinfunction "VDD_100") (pintype "power_in"))
      (node (ref "U1") (pin "11") (pinfunction "VDD_11") (pintype "power_in"))
      (node (ref "U1") (pin "19") (pinfunction "VDD_19") (pintype "power_in"))
      (node (ref "U1") (pin "21") (pinfunction "VREF+_21") (pintype "power_in"))
      (node (ref "U1") (pin "22") (pinfunction "VDDA_22") (pintype "power_in"))
      (node (ref "U1") (pin "28") (pinfunction "VDD_28") (pintype "power_in"))
      (node (ref "U1") (pin "50") (pinfunction "VDD_50") (pintype "power_in"))
      (node (ref "U1") (pin "75") (pinfunction "VDD_75") (pintype "power_in"))
      (node (ref "U2") (pin "3") (pinfunction "~{WP}_(IO2)_3") (pintype "bidirectional"))
      (node (ref "U2") (pin "7") (pinfunction "~{HOLD}/~{RESET}_(IO3)_7") (pintype "bidirectional"))
      (node (ref "U2") (pin "8") (pinfunction "VCC_8") (pintype "power_in"))
      (node (ref "U3") (pin "8") (pinfunction "VDD_8") (pintype "passive"))
      (node (ref "U4") (pin "5") (pinfunction "VDDAON_5") (pintype "power_in"))
      (node (ref "U4") (pin "6") (pinfunction "VDD3V3_6") (pintype "power_in"))
      (node (ref "U4") (pin "7") (pinfunction "VDD3V3_7") (pintype "power_in"))
      (node (ref "U5") (pin "3") (pinfunction "3.3V_3") (pintype "power_in"))
    )
    (net (code "2") (name "+12") (class "Default")
      (node (ref "C20") (pin "2") (pinfunction "2_2") (pintype "passive"))
      (node (ref "D3") (pin "2") (pinfunction "K_2") (pintype "passive"))
      (node (ref "F1") (pin "2") (pinfunction "2_2") (pintype "passive"))
      (node (ref "H2") (pin "1") (pinfunction "1_1") (pintype "passive"))
      (node (ref "H5") (pin "1") (pinfunction "1_1") (pintype "passive"))
      (node (ref "IC1") (pin "2") (pinfunction "A_2") (pintype "passive"))
      (node (ref "IC2") (pin "2") (pinfunction "IN_2") (pintype "passive"))
      (node (ref "Q3") (pin "4") (pinfunction "C_4") (pintype "passive"))
      (node (ref "R9") (pin "1") (pinfunction "1_1") (pintype "passive"))
    )
    (net (code "3") (name "/-LED") (class "Default")
      (node (ref "H5") (pin "2") (pinfunction "2_2") (pintype "passive"))
      (node (ref "Q4") (pin "2") (pinfunction "DRAIN_2") (pintype "passive"))
    )
    (net (code "4") (name "/-SIREN") (class "Default")
      (node (ref "H2") (pin "2") (pinfunction "2_2") (pintype "passive"))
      (node (ref "Q2") (pin "2") (pinfunction "DRAIN_2") (pintype "passive"))
    )
    (net (code "5") (name "/12VDC") (class "Default")
      (node (ref "D2") (pin "2") (pinfunction "A_2") (pintype "passive"))
      (node (ref "KF1") (pin "1") (pinfunction "1_1") (pintype "passive"))
    )
    (net (code "6") (name "/BOOT0") (class "Default")
      (node (ref "R5") (pin "2") (pinfunction "2_2") (pintype "passive"))
      (node (ref "U1") (pin "94") (pinfunction "BOOT0_94") (pintype "input"))
    )
    (net (code "7") (name "/F_CS") (class "Default")
      (node (ref "R2") (pin "1") (pinfunction "1_1") (pintype "passive"))
      (node (ref "U1") (pin "35") (pinfunction "PB0_35") (pintype "bidirectional"))
      (node (ref "U2") (pin "1") (pinfunction "~{CS}_1") (pintype "input"))
    )
    (net (code "8") (name "/LED") (class "Default")
      (node (ref "R41") (pin "2") (pinfunction "2_2") (pintype "passive"))
      (node (ref "R8") (pin "2") (pinfunction "2_2") (pintype "passive"))
      (node (ref "U1") (pin "32") (pinfunction "PA7_32") (pintype "bidirectional"))
    )
    (net (code "9") (name "/LORADIO") (class "Default")
      (node (ref "U1") (pin "55") (pinfunction "PD8_55") (pintype "bidirectional"))
      (node (ref "U5") (pin "5") (pinfunction "DI00_5") (pintype "bidirectional"))
    )
    (net (code "10") (name "/LORARST") (class "Default")
      (node (ref "U1") (pin "56") (pinfunction "PD9_56") (pintype "bidirectional"))
      (node (ref "U5") (pin "4") (pinfunction "RESET_4") (pintype "input"))
    )
    (net (code "11") (name "/LORASS") (class "Default")
      (node (ref "U1") (pin "36") (pinfunction "PB1_36") (pintype "bidirectional"))
      (node (ref "U5") (pin "15") (pinfunction "NSS_15") (pintype "input"))
    )
    (net (code "12") (name "/MISO1") (class "Default")
      (node (ref "U1") (pin "90") (pinfunction "PB4(NJTRST)_90") (pintype "bidirectional"))
      (node (ref "U4") (pin "19") (pinfunction "SPIMISO_19") (pintype "output"))
    )
    (net (code "13") (name "/MISO2") (class "Default")
      (node (ref "U1") (pin "53") (pinfunction "PB14_53") (pintype "bidirectional"))
      (node (ref "U2") (pin "2") (pinfunction "DO_(IO1)_2") (pintype "bidirectional"))
      (node (ref "U5") (pin "13") (pinfunction "MISO_13") (pintype "output"))
    )
    (net (code "14") (name "/MOSI1") (class "Default")
      (node (ref "U1") (pin "91") (pinfunction "PB5_91") (pintype "bidirectional"))
      (node (ref "U4") (pin "18") (pinfunction "SPIMOSI_18") (pintype "input"))
    )
    (net (code "15") (name "/MOSI2") (class "Default")
      (node (ref "U1") (pin "54") (pinfunction "PB15_54") (pintype "bidirectional"))
      (node (ref "U2") (pin "5") (pinfunction "DI_(IO0)_5") (pintype "bidirectional"))
      (node (ref "U5") (pin "14") (pinfunction "MOSI_14") (pintype "input"))
    )
    (net (code "16") (name "/RELAY") (class "Default")
      (node (ref "KF2") (pin "2") (pinfunction "2_2") (pintype "passive"))
      (node (ref "R42") (pin "2") (pinfunction "2_2") (pintype "passive"))
      (node (ref "U1") (pin "45") (pinfunction "PE14_45") (pintype "bidirectional"))
    )
    (net (code "17") (name "/RST") (class "Default")
      (node (ref "BT2") (pin "1") (pinfunction "1_1") (pintype "passive"))
      (node (ref "C14") (pin "1") (pinfunction "1_1") (pintype "passive"))
      (node (ref "JP5") (pin "1") (pinfunction "1_1") (pintype "passive"))
      (node (ref "R1") (pin "1") (pinfunction "1_1") (pintype "passive"))
      (node (ref "U1") (pin "14") (pinfunction "NRST_14") (pintype "bidirectional"))
    )
    (net (code "18") (name "/RX_ESP") (class "Default")
      (node (ref "JP2") (pin "3") (pinfunction "3_3") (pintype "passive"))
      (node (ref "R18") (pin "1") (pinfunction "1_1") (pintype "passive"))
      (node (ref "U3") (pin "15") (pinfunction "GPIO3/RXD0_15") (pintype "passive"))
    )
    (net (code "19") (name "/RX_ESP1") (class "Default")
      (node (ref "R18") (pin "2") (pinfunction "2_2") (pintype "passive"))
      (node (ref "U1") (pin "25") (pinfunction "PA2_25") (pintype "bidirectional"))
    )
    (net (code "20") (name "/RX{slash}PA10") (class "Default")
      (node (ref "JP3") (pin "1") (pinfunction "1_1") (pintype "passive"))
      (node (ref "U1") (pin "69") (pinfunction "PA10_69") (pintype "bidirectional"))
    )
    (net (code "21") (name "/SCK1") (class "Default")
      (node (ref "U1") (pin "89") (pinfunction "PB3(JTDO/TRACESWO)_89") (pintype "bidirectional"))
      (node (ref "U4") (pin "20") (pinfunction "SPICLK_20") (pintype "input"))
    )
    (net (code "22") (name "/SCK2") (class "Default")
      (node (ref "R4") (pin "2") (pinfunction "2_2") (pintype "passive"))
      (node (ref "U1") (pin "52") (pinfunction "PB13_52") (pintype "bidirectional"))
      (node (ref "U5") (pin "12") (pinfunction "SCK_12") (pintype "input"))
    )
    (net (code "23") (name "/SDIO_CMD") (class "Default")
      (node (ref "P1") (pin "2") (pinfunction "[MOSI]_DI_2") (pintype "passive"))
      (node (ref "R19") (pin "1") (pinfunction "1_1") (pintype "passive"))
      (node (ref "U1") (pin "83") (pinfunction "PD2_83") (pintype "bidirectional"))
    )
    (net (code "24") (name "/SDIO_D0") (class "Default")
      (node (ref "P1") (pin "7") (pinfunction "[MISO]_DO_7") (pintype "passive"))
      (node (ref "R24") (pin "1") (pinfunction "1_1") (pintype "passive"))
      (node (ref "U1") (pin "65") (pinfunction "PC8_65") (pintype "bidirectional"))
    )
    (net (code "25") (name "/SDIO_D1") (class "Default")
      (node (ref "P1") (pin "8") (pinfunction "NC/nIRQ_8") (pintype "passive"))
      (node (ref "R28") (pin "1") (pinfunction "1_1") (pintype "passive"))
      (node (ref "U1") (pin "66") (pinfunction "PC9_66") (pintype "bidirectional"))
    )
    (net (code "26") (name "/SDIO_D2") (class "Default")
      (node (ref "P1") (pin "9") (pinfunction "NC_9") (pintype "passive"))
      (node (ref "R10") (pin "1") (pinfunction "1_1") (pintype "passive"))
      (node (ref "U1") (pin "78") (pinfunction "PC10_78") (pintype "bidirectional"))
    )
    (net (code "27") (name "/SDIO_D3") (class "Default")
      (node (ref "P1") (pin "1") (pinfunction "nCS_1") (pintype "passive"))
      (node (ref "R15") (pin "1") (pinfunction "1_1") (pintype "passive"))
      (node (ref "U1") (pin "79") (pinfunction "PC11_79") (pintype "bidirectional"))
    )
    (net (code "28") (name "/SDIO_SCK") (class "Default")
      (node (ref "P1") (pin "5") (pinfunction "CLK_5") (pintype "passive"))
      (node (ref "R21") (pin "1") (pinfunction "1_1") (pintype "passive"))
      (node (ref "U1") (pin "80") (pinfunction "PC12_80") (pintype "bidirectional"))
    )
    (net (code "29") (name "/SIREN") (class "Default")
      (node (ref "D4") (pin "2") (pinfunction "K_2") (pintype "passive"))
      (node (ref "R38") (pin "2") (pinfunction "2_2") (pintype "passive"))
      (node (ref "R6") (pin "2") (pinfunction "2_2") (pintype "passive"))
      (node (ref "R7") (pin "1") (pinfunction "1_1") (pintype "passive"))
      (node (ref "U1") (pin "31") (pinfunction "PA6_31") (pintype "bidirectional"))
    )
    (net (code "30") (name "/SWCLK") (class "Default")
      (node (ref "JP1") (pin "3") (pinfunction "3_3") (pintype "passive"))
      (node (ref "U1") (pin "76") (pinfunction "PA14(JTCK-SWCLK)_76") (pintype "bidirectional"))
    )
    (net (code "31") (name "/SWDIO") (class "Default")
      (node (ref "JP1") (pin "2") (pinfunction "2_2") (pintype "passive"))
      (node (ref "U1") (pin "72") (pinfunction "PA13(JTMS-SWDIO)_72") (pintype "bidirectional"))
    )
    (net (code "32") (name "/TX_ESP") (class "Default")
      (node (ref "JP2") (pin "2") (pinfunction "2_2") (pintype "passive"))
      (node (ref "R20") (pin "1") (pinfunction "1_1") (pintype "passive"))
      (node (ref "U3") (pin "16") (pinfunction "GPIO1/SPICS1/TXD0_16") (pintype "passive"))
    )
    (net (code "33") (name "/TX_ESP1") (class "Default")
      (node (ref "R20") (pin "2") (pinfunction "2_2") (pintype "passive"))
      (node (ref "U1") (pin "26") (pinfunction "PA3_26") (pintype "bidirectional"))
    )
    (net (code "34") (name "/TX{slash}PA9") (class "Default")
      (node (ref "JP3") (pin "2") (pinfunction "2_2") (pintype "passive"))
      (node (ref "U1") (pin "68") (pinfunction "PA9_68") (pintype "bidirectional"))
    )
    (net (code "35") (name "/UWBCS") (class "Default")
      (node (ref "U1") (pin "29") (pinfunction "PA4_29") (pintype "bidirectional"))
      (node (ref "U4") (pin "17") (pinfunction "~{SPICS}_17") (pintype "input"))
    )
    (net (code "36") (name "/UWBEXT") (class "Default")
      (node (ref "R39") (pin "2") (pinfunction "2_2") (pintype "passive"))
      (node (ref "U1") (pin "17") (pinfunction "PC2_17") (pintype "bidirectional"))
    )
    (net (code "37") (name "/UWBIRQ") (class "Default")
      (node (ref "R27") (pin "2") (pinfunction "2_2") (pintype "passive"))
      (node (ref "U1") (pin "16") (pinfunction "PC1_16") (pintype "bidirectional"))
      (node (ref "U4") (pin "22") (pinfunction "IRQ/GPIO8_22") (pintype "bidirectional"))
    )
    (net (code "38") (name "/UWBRST") (class "Default")
      (node (ref "U1") (pin "15") (pinfunction "PC0_15") (pintype "bidirectional"))
      (node (ref "U4") (pin "3") (pinfunction "~{RST}_3") (pintype "bidirectional"))
    )
    (net (code "39") (name "/UWBWAKEUP") (class "Default")
      (node (ref "R40") (pin "2") (pinfunction "2_2") (pintype "passive"))
      (node (ref "U1") (pin "18") (pinfunction "PC3_18") (pintype "bidirectional"))
    )
    (net (code "40") (name "/VBAT") (class "Default")
      (node (ref "C12") (pin "1") (pinfunction "1_1") (pintype "passive"))
      (node (ref "D1") (pin "3") (pinfunction "K_3") (pintype "passive"))
      (node (ref "U1") (pin "6") (pinfunction "VBAT_6") (pintype "power_in"))
    )
    (net (code "41") (name "GND") (class "Default")
      (node (ref "BT1") (pin "2") (pinfunction "GND_2") (pintype "passive"))
      (node (ref "BT2") (pin "2") (pinfunction "2_2") (pintype "passive"))
      (node (ref "BT3") (pin "2") (pinfunction "2_2") (pintype "passive"))
      (node (ref "C1") (pin "2") (pinfunction "2_2") (pintype "passive"))
      (node (ref "C10") (pin "2") (pinfunction "2_2") (pintype "passive"))
      (node (ref "C11") (pin "1") (pinfunction "1_1") (pintype "passive"))
      (node (ref "C12") (pin "2") (pinfunction "2_2") (pintype "passive"))
      (node (ref "C13") (pin "2") (pinfunction "2_2") (pintype "passive"))
      (node (ref "C14") (pin "2") (pinfunction "2_2") (pintype "passive"))
      (node (ref "C15") (pin "1") (pinfunction "1_1") (pintype "passive"))
      (node (ref "C16") (pin "1") (pinfunction "1_1") (pintype "passive"))
      (node (ref "C17") (pin "2") (pinfunction "2_2") (pintype "passive"))
      (node (ref "C18") (pin "1") (pinfunction "1_1") (pintype "passive"))
      (node (ref "C2") (pin "2") (pinfunction "2_2") (pintype "passive"))
      (node (ref "C20") (pin "1") (pinfunction "1_1") (pintype "passive"))
      (node (ref "C21") (pin "2") (pinfunction "2_2") (pintype "passive"))
      (node (ref "C22") (pin "2") (pinfunction "2_2") (pintype "passive"))
      (node (ref "C23") (pin "1") (pinfunction "1_1") (pintype "passive"))
      (node (ref "C25") (pin "1") (pinfunction "1_1") (pintype "passive"))
      (node (ref "C26") (pin "1") (pinfunction "1_1") (pintype "passive"))
      (node (ref "C27") (pin "2") (pinfunction "2_2") (pintype "passive"))
      (node (ref "C28") (pin "2") (pinfunction "2_2") (pintype "passive"))
      (node (ref "C29") (pin "2") (pinfunction "2_2") (pintype "passive"))
      (node (ref "C3") (pin "2") (pinfunction "2_2") (pintype "passive"))
      (node (ref "C30") (pin "2") (pinfunction "2_2") (pintype "passive"))
      (node (ref "C31") (pin "2") (pinfunction "2_2") (pintype "passive"))
      (node (ref "C4") (pin "2") (pinfunction "2_2") (pintype "passive"))
      (node (ref "C5") (pin "2") (pinfunction "2_2") (pintype "passive"))
      (node (ref "C6") (pin "2") (pinfunction "2_2") (pintype "passive"))
      (node (ref "C7") (pin "2") (pinfunction "2_2") (pintype "passive"))
      (node (ref "C8") (pin "2") (pinfunction "2_2") (pintype "passive"))
      (node (ref "C9") (pin "2") (pinfunction "2_2") (pintype "passive"))
      (node (ref "D4") (pin "1") (pinfunction "A_1") (pintype "passive"))
      (node (ref "H3") (pin "2") (pinfunction "2_2") (pintype "passive"))
      (node (ref "IC1") (pin "1") (pinfunction "K_1") (pintype "passive"))
      (node (ref "IC2") (pin "4") (pinfunction "GND_4") (pintype "power_in"))
      (node (ref "JP1") (pin "1") (pinfunction "1_1") (pintype "passive"))
      (node (ref "JP2") (pin "1") (pinfunction "1_1") (pintype "passive"))
      (node (ref "JP3") (pin "3") (pinfunction "3_3") (pintype "passive"))
      (node (ref "KF1") (pin "2") (pinfunction "2_2") (pintype "passive"))
      (node (ref "KF2") (pin "1") (pinfunction "1_1") (pintype "passive"))
      (node (ref "L2") (pin "2") (pinfunction "K_2") (pintype "passive"))
      (node (ref "L3") (pin "2") (pinfunction "K_2") (pintype "passive"))
      (node (ref "L4") (pin "2") (pinfunction "K_2") (pintype "passive"))
      (node (ref "L5") (pin "2") (pinfunction "K_2") (pintype "passive"))
      (node (ref "P1") (pin "3") (pinfunction "Detech_3") (pintype "passive"))
      (node (ref "P1") (pin "6") (pinfunction "VSS_6") (pintype "passive"))
      (node (ref "Q2") (pin "3") (pinfunction "SOURCE_3") (pintype "passive"))
      (node (ref "Q3") (pin "2") (pinfunction "C_2") (pintype "passive"))
      (node (ref "Q4") (pin "3") (pinfunction "SOURCE_3") (pintype "passive"))
      (node (ref "R11") (pin "2") (pinfunction "2_2") (pintype "passive"))
      (node (ref "R12") (pin "1") (pinfunction "1_1") (pintype "passive"))
      (node (ref "R14") (pin "2") (pinfunction "2_2") (pintype "passive"))
      (node (ref "R17") (pin "2") (pinfunction "2_2") (pintype "passive"))
      (node (ref "R26") (pin "2") (pinfunction "2_2") (pintype "passive"))
      (node (ref "R27") (pin "1") (pinfunction "1_1") (pintype "passive"))
      (node (ref "R5") (pin "1") (pinfunction "1_1") (pintype "passive"))
      (node (ref "R7") (pin "2") (pinfunction "2_2") (pintype "passive"))
      (node (ref "U1") (pin "10") (pinfunction "VSS_10") (pintype "power_in"))
      (node (ref "U1") (pin "20") (pinfunction "VSSA_20") (pintype "power_in"))
      (node (ref "U1") (pin "27") (pinfunction "VSS_27") (pintype "power_in"))
      (node (ref "U1") (pin "74") (pinfunction "VSS_74") (pintype "power_in"))
      (node (ref "U1") (pin "99") (pinfunction "VSS_99") (pintype "power_in"))
      (node (ref "U2") (pin "4") (pinfunction "GND_4") (pintype "power_in"))
      (node (ref "U3") (pin "9") (pinfunction "GND_9") (pintype "passive"))
      (node (ref "U4") (pin "16") (pinfunction "GND_16") (pintype "power_in"))
      (node (ref "U4") (pin "21") (pinfunction "GND_21") (pintype "power_in"))
      (node (ref "U4") (pin "23") (pinfunction "GND_23") (pintype "power_in"))
      (node (ref "U4") (pin "24") (pinfunction "GND_24") (pintype "power_in"))
      (node (ref "U4") (pin "8") (pinfunction "GND_8") (pintype "power_in"))
      (node (ref "U5") (pin "1") (pinfunction "GND_1") (pintype "power_in"))
      (node (ref "U5") (pin "16") (pinfunction "GND_16") (pintype "power_in"))
      (node (ref "U5") (pin "2") (pinfunction "GND_2") (pintype "power_in"))
      (node (ref "U5") (pin "9") (pinfunction "GND_9") (pintype "power_in"))
    )
    (net (code "42") (name "Net-(BT1-+3V)") (class "Default")
      (node (ref "BT1") (pin "1") (pinfunction "+3V_1") (pintype "passive"))
      (node (ref "D1") (pin "2") (pinfunction "A_2") (pintype "passive"))
    )
    (net (code "43") (name "Net-(C24-Pad2)") (class "Default")
      (node (ref "C24") (pin "2") (pinfunction "2_2") (pintype "passive"))
      (node (ref "R17") (pin "1") (pinfunction "1_1") (pintype "passive"))
    )
    (net (code "44") (name "Net-(D2-C)") (class "Default")
      (node (ref "D2") (pin "1") (pinfunction "C_1") (pintype "passive"))
      (node (ref "F1") (pin "1") (pinfunction "1_1") (pintype "passive"))
    )
    (net (code "45") (name "Net-(D3-A)") (class "Default")
      (node (ref "C21") (pin "1") (pinfunction "1_1") (pintype "passive"))
      (node (ref "D3") (pin "1") (pinfunction "A_1") (pintype "passive"))
      (node (ref "IC1") (pin "3") (pinfunction "G_3") (pintype "passive"))
      (node (ref "R12") (pin "2") (pinfunction "2_2") (pintype "passive"))
    )
    (net (code "46") (name "Net-(IC2-BS)") (class "Default")
      (node (ref "C19") (pin "1") (pinfunction "1_1") (pintype "passive"))
      (node (ref "IC2") (pin "1") (pinfunction "BS_1") (pintype "passive"))
    )
    (net (code "47") (name "Net-(IC2-COMP)") (class "Default")
      (node (ref "C24") (pin "1") (pinfunction "1_1") (pintype "passive"))
      (node (ref "IC2") (pin "6") (pinfunction "COMP_6") (pintype "passive"))
    )
    (net (code "48") (name "Net-(IC2-EN)") (class "Default")
      (node (ref "IC2") (pin "7") (pinfunction "EN_7") (pintype "passive"))
      (node (ref "R9") (pin "2") (pinfunction "2_2") (pintype "passive"))
    )
    (net (code "49") (name "Net-(IC2-FB)") (class "Default")
      (node (ref "IC2") (pin "5") (pinfunction "FB_5") (pintype "passive"))
      (node (ref "R13") (pin "1") (pinfunction "1_1") (pintype "passive"))
      (node (ref "R14") (pin "1") (pinfunction "1_1") (pintype "passive"))
    )
    (net (code "50") (name "Net-(IC2-SS)") (class "Default")
      (node (ref "C22") (pin "1") (pinfunction "1_1") (pintype "passive"))
      (node (ref "IC2") (pin "8") (pinfunction "SS_8") (pintype "passive"))
    )
    (net (code "51") (name "Net-(IC2-SW)") (class "Default")
      (node (ref "C19") (pin "2") (pinfunction "2_2") (pintype "passive"))
      (node (ref "IC2") (pin "3") (pinfunction "SW_3") (pintype "passive"))
      (node (ref "L1") (pin "1") (pinfunction "1_1") (pintype "passive"))
    )
    (net (code "52") (name "Net-(L2-A)") (class "Default")
      (node (ref "L2") (pin "1") (pinfunction "A_1") (pintype "passive"))
      (node (ref "R38") (pin "1") (pinfunction "1_1") (pintype "passive"))
    )
    (net (code "53") (name "Net-(L3-A)") (class "Default")
      (node (ref "L3") (pin "1") (pinfunction "A_1") (pintype "passive"))
      (node (ref "R16") (pin "1") (pinfunction "1_1") (pintype "passive"))
    )
    (net (code "54") (name "Net-(L4-A)") (class "Default")
      (node (ref "L4") (pin "1") (pinfunction "A_1") (pintype "passive"))
      (node (ref "R41") (pin "1") (pinfunction "1_1") (pintype "passive"))
    )
    (net (code "55") (name "Net-(L5-A)") (class "Default")
      (node (ref "L5") (pin "1") (pinfunction "A_1") (pintype "passive"))
      (node (ref "R42") (pin "1") (pinfunction "1_1") (pintype "passive"))
    )
    (net (code "56") (name "Net-(Q2-GATE)") (class "Default")
      (node (ref "Q2") (pin "1") (pinfunction "GATE_1") (pintype "passive"))
      (node (ref "R6") (pin "1") (pinfunction "1_1") (pintype "passive"))
    )
    (net (code "57") (name "Net-(Q3-A)") (class "Default")
      (node (ref "Q3") (pin "1") (pinfunction "A_1") (pintype "passive"))
      (node (ref "R8") (pin "1") (pinfunction "1_1") (pintype "passive"))
    )
    (net (code "58") (name "Net-(Q3-E)") (class "Default")
      (node (ref "Q3") (pin "3") (pinfunction "E_3") (pintype "passive"))
      (node (ref "Q4") (pin "1") (pinfunction "GATE_1") (pintype "passive"))
      (node (ref "R11") (pin "1") (pinfunction "1_1") (pintype "passive"))
    )
    (net (code "59") (name "Net-(U1A-PC14-OSC32_IN(PC14))") (class "Default")
      (node (ref "C10") (pin "1") (pinfunction "1_1") (pintype "passive"))
      (node (ref "U1") (pin "8") (pinfunction "PC14-OSC32_IN(PC14)_8") (pintype "bidirectional"))
      (node (ref "Y1") (pin "2") (pinfunction "2_2") (pintype "passive"))
    )
    (net (code "60") (name "Net-(U1A-PC15-OSC32_OUT(PC15))") (class "Default")
      (node (ref "C13") (pin "1") (pinfunction "1_1") (pintype "passive"))
      (node (ref "U1") (pin "9") (pinfunction "PC15-OSC32_OUT(PC15)_9") (pintype "bidirectional"))
      (node (ref "Y1") (pin "1") (pinfunction "1_1") (pintype "passive"))
    )
    (net (code "61") (name "Net-(U1A-PH0-OSC_IN(PH0))") (class "Default")
      (node (ref "C11") (pin "2") (pinfunction "2_2") (pintype "passive"))
      (node (ref "R3") (pin "2") (pinfunction "2_2") (pintype "passive"))
      (node (ref "U1") (pin "12") (pinfunction "PH0-OSC_IN(PH0)_12") (pintype "bidirectional"))
      (node (ref "Y2") (pin "2") (pinfunction "2_2") (pintype "passive"))
    )
    (net (code "62") (name "Net-(U1A-PH1-OSC_OUT(PH1))") (class "Default")
      (node (ref "C15") (pin "2") (pinfunction "2_2") (pintype "passive"))
      (node (ref "R3") (pin "1") (pinfunction "1_1") (pintype "passive"))
      (node (ref "U1") (pin "13") (pinfunction "PH1-OSC_OUT(PH1)_13") (pintype "bidirectional"))
      (node (ref "Y2") (pin "1") (pinfunction "1_1") (pintype "passive"))
    )
    (net (code "63") (name "Net-(U1A-VCAP_1)") (class "Default")
      (node (ref "C16") (pin "2") (pinfunction "2_2") (pintype "passive"))
      (node (ref "U1") (pin "49") (pinfunction "VCAP_1_49") (pintype "power_in"))
    )
    (net (code "64") (name "Net-(U1A-VCAP_2)") (class "Default")
      (node (ref "C18") (pin "2") (pinfunction "2_2") (pintype "passive"))
      (node (ref "U1") (pin "73") (pinfunction "VCAP_2_73") (pintype "power_in"))
    )
    (net (code "65") (name "Net-(U2-CLK)") (class "Default")
      (node (ref "R4") (pin "1") (pinfunction "1_1") (pintype "passive"))
      (node (ref "U2") (pin "6") (pinfunction "CLK_6") (pintype "input"))
    )
    (net (code "66") (name "Net-(U3-EN)") (class "Default")
      (node (ref "R23") (pin "1") (pinfunction "1_1") (pintype "passive"))
      (node (ref "U3") (pin "3") (pinfunction "EN_3") (pintype "passive"))
    )
    (net (code "67") (name "Net-(U3-GPIO0{slash}SPICS2)") (class "Default")
      (node (ref "BT3") (pin "1") (pinfunction "1_1") (pintype "passive"))
      (node (ref "R25") (pin "1") (pinfunction "1_1") (pintype "passive"))
      (node (ref "U3") (pin "12") (pinfunction "GPIO0/SPICS2_12") (pintype "passive"))
    )
    (net (code "68") (name "Net-(U3-GPIO15{slash}HSPICS{slash}RTS0{slash}TXD2)") (class "Default")
      (node (ref "R26") (pin "1") (pinfunction "1_1") (pintype "passive"))
      (node (ref "U3") (pin "10") (pinfunction "GPIO15/HSPICS/RTS0/TXD2_10") (pintype "passive"))
    )
    (net (code "69") (name "Net-(U3-~{RST})") (class "Default")
      (node (ref "R22") (pin "1") (pinfunction "1_1") (pintype "passive"))
      (node (ref "U3") (pin "1") (pinfunction "~{RST}_1") (pintype "passive"))
    )
    (net (code "70") (name "Net-(U4-EXTON)") (class "Default")
      (node (ref "R39") (pin "1") (pinfunction "1_1") (pintype "passive"))
      (node (ref "U4") (pin "1") (pinfunction "EXTON_1") (pintype "output"))
    )
    (net (code "71") (name "Net-(U4-WAKEUP)") (class "Default")
      (node (ref "R40") (pin "1") (pinfunction "1_1") (pintype "passive"))
      (node (ref "U4") (pin "2") (pinfunction "WAKEUP_2") (pintype "bidirectional"))
    )
    (net (code "72") (name "unconnected-(JP1-Pad4)") (class "Default")
      (node (ref "JP1") (pin "4") (pinfunction "4_4") (pintype "passive"))
    )
    (net (code "73") (name "unconnected-(P1-GND-Pad0)") (class "Default")
      (node (ref "P1") (pin "0") (pinfunction "GND_0") (pintype "passive"))
    )
    (net (code "74") (name "unconnected-(U1A-PA0-WKUP(PA0)-Pad23)") (class "Default")
      (node (ref "U1") (pin "23") (pinfunction "PA0-WKUP(PA0)_23") (pintype "bidirectional"))
    )
    (net (code "75") (name "unconnected-(U1A-PA1-Pad24)") (class "Default")
      (node (ref "U1") (pin "24") (pinfunction "PA1_24") (pintype "bidirectional"))
    )
    (net (code "76") (name "unconnected-(U1A-PA5-Pad30)") (class "Default")
      (node (ref "U1") (pin "30") (pinfunction "PA5_30") (pintype "bidirectional"))
    )
    (net (code "77") (name "unconnected-(U1A-PA8-Pad67)") (class "Default")
      (node (ref "U1") (pin "67") (pinfunction "PA8_67") (pintype "bidirectional"))
    )
    (net (code "78") (name "unconnected-(U1A-PA11-Pad70)") (class "Default")
      (node (ref "U1") (pin "70") (pinfunction "PA11_70") (pintype "bidirectional"))
    )
    (net (code "79") (name "unconnected-(U1A-PA12-Pad71)") (class "Default")
      (node (ref "U1") (pin "71") (pinfunction "PA12_71") (pintype "bidirectional"))
    )
    (net (code "80") (name "unconnected-(U1A-PA15(JTDI)-Pad77)") (class "Default")
      (node (ref "U1") (pin "77") (pinfunction "PA15(JTDI)_77") (pintype "bidirectional"))
    )
    (net (code "81") (name "unconnected-(U1A-PB2-BOOT1(PB2)-Pad37)") (class "Default")
      (node (ref "U1") (pin "37") (pinfunction "PB2-BOOT1(PB2)_37") (pintype "bidirectional"))
    )
    (net (code "82") (name "unconnected-(U1A-PB6-Pad92)") (class "Default")
      (node (ref "U1") (pin "92") (pinfunction "PB6_92") (pintype "bidirectional"))
    )
    (net (code "83") (name "unconnected-(U1A-PB7-Pad93)") (class "Default")
      (node (ref "U1") (pin "93") (pinfunction "PB7_93") (pintype "bidirectional"))
    )
    (net (code "84") (name "unconnected-(U1A-PB8-Pad95)") (class "Default")
      (node (ref "U1") (pin "95") (pinfunction "PB8_95") (pintype "bidirectional"))
    )
    (net (code "85") (name "unconnected-(U1A-PB9-Pad96)") (class "Default")
      (node (ref "U1") (pin "96") (pinfunction "PB9_96") (pintype "bidirectional"))
    )
    (net (code "86") (name "unconnected-(U1A-PB10-Pad47)") (class "Default")
      (node (ref "U1") (pin "47") (pinfunction "PB10_47") (pintype "bidirectional"))
    )
    (net (code "87") (name "unconnected-(U1A-PB11-Pad48)") (class "Default")
      (node (ref "U1") (pin "48") (pinfunction "PB11_48") (pintype "bidirectional"))
    )
    (net (code "88") (name "unconnected-(U1A-PB12-Pad51)") (class "Default")
      (node (ref "U1") (pin "51") (pinfunction "PB12_51") (pintype "bidirectional"))
    )
    (net (code "89") (name "unconnected-(U1A-PC4-Pad33)") (class "Default")
      (node (ref "U1") (pin "33") (pinfunction "PC4_33") (pintype "bidirectional"))
    )
    (net (code "90") (name "unconnected-(U1A-PC5-Pad34)") (class "Default")
      (node (ref "U1") (pin "34") (pinfunction "PC5_34") (pintype "bidirectional"))
    )
    (net (code "91") (name "unconnected-(U1A-PC6-Pad63)") (class "Default")
      (node (ref "U1") (pin "63") (pinfunction "PC6_63") (pintype "bidirectional"))
    )
    (net (code "92") (name "unconnected-(U1A-PC7-Pad64)") (class "Default")
      (node (ref "U1") (pin "64") (pinfunction "PC7_64") (pintype "bidirectional"))
    )
    (net (code "93") (name "unconnected-(U1A-PC13-Pad7)") (class "Default")
      (node (ref "U1") (pin "7") (pinfunction "PC13_7") (pintype "bidirectional"))
    )
    (net (code "94") (name "unconnected-(U1A-PD0-Pad81)") (class "Default")
      (node (ref "U1") (pin "81") (pinfunction "PD0_81") (pintype "bidirectional"))
    )
    (net (code "95") (name "unconnected-(U1A-PD1-Pad82)") (class "Default")
      (node (ref "U1") (pin "82") (pinfunction "PD1_82") (pintype "bidirectional"))
    )
    (net (code "96") (name "unconnected-(U1A-PD3-Pad84)") (class "Default")
      (node (ref "U1") (pin "84") (pinfunction "PD3_84") (pintype "bidirectional"))
    )
    (net (code "97") (name "unconnected-(U1A-PD4-Pad85)") (class "Default")
      (node (ref "U1") (pin "85") (pinfunction "PD4_85") (pintype "bidirectional"))
    )
    (net (code "98") (name "unconnected-(U1A-PD5-Pad86)") (class "Default")
      (node (ref "U1") (pin "86") (pinfunction "PD5_86") (pintype "bidirectional"))
    )
    (net (code "99") (name "unconnected-(U1A-PD6-Pad87)") (class "Default")
      (node (ref "U1") (pin "87") (pinfunction "PD6_87") (pintype "bidirectional"))
    )
    (net (code "100") (name "unconnected-(U1A-PD7-Pad88)") (class "Default")
      (node (ref "U1") (pin "88") (pinfunction "PD7_88") (pintype "bidirectional"))
    )
    (net (code "101") (name "unconnected-(U1A-PD10-Pad57)") (class "Default")
      (node (ref "U1") (pin "57") (pinfunction "PD10_57") (pintype "bidirectional"))
    )
    (net (code "102") (name "unconnected-(U1A-PD11-Pad58)") (class "Default")
      (node (ref "U1") (pin "58") (pinfunction "PD11_58") (pintype "bidirectional"))
    )
    (net (code "103") (name "unconnected-(U1A-PD12-Pad59)") (class "Default")
      (node (ref "U1") (pin "59") (pinfunction "PD12_59") (pintype "bidirectional"))
    )
    (net (code "104") (name "unconnected-(U1A-PD13-Pad60)") (class "Default")
      (node (ref "U1") (pin "60") (pinfunction "PD13_60") (pintype "bidirectional"))
    )
    (net (code "105") (name "unconnected-(U1A-PD14-Pad61)") (class "Default")
      (node (ref "U1") (pin "61") (pinfunction "PD14_61") (pintype "bidirectional"))
    )
    (net (code "106") (name "unconnected-(U1A-PD15-Pad62)") (class "Default")
      (node (ref "U1") (pin "62") (pinfunction "PD15_62") (pintype "bidirectional"))
    )
    (net (code "107") (name "unconnected-(U1A-PE0-Pad97)") (class "Default")
      (node (ref "U1") (pin "97") (pinfunction "PE0_97") (pintype "bidirectional"))
    )
    (net (code "108") (name "unconnected-(U1A-PE1-Pad98)") (class "Default")
      (node (ref "U1") (pin "98") (pinfunction "PE1_98") (pintype "bidirectional"))
    )
    (net (code "109") (name "unconnected-(U1A-PE2-Pad1)") (class "Default")
      (node (ref "U1") (pin "1") (pinfunction "PE2_1") (pintype "bidirectional"))
    )
    (net (code "110") (name "unconnected-(U1A-PE3-Pad2)") (class "Default")
      (node (ref "U1") (pin "2") (pinfunction "PE3_2") (pintype "bidirectional"))
    )
    (net (code "111") (name "unconnected-(U1A-PE4-Pad3)") (class "Default")
      (node (ref "U1") (pin "3") (pinfunction "PE4_3") (pintype "bidirectional"))
    )
    (net (code "112") (name "unconnected-(U1A-PE5-Pad4)") (class "Default")
      (node (ref "U1") (pin "4") (pinfunction "PE5_4") (pintype "bidirectional"))
    )
    (net (code "113") (name "unconnected-(U1A-PE6-Pad5)") (class "Default")
      (node (ref "U1") (pin "5") (pinfunction "PE6_5") (pintype "bidirectional"))
    )
    (net (code "114") (name "unconnected-(U1A-PE7-Pad38)") (class "Default")
      (node (ref "U1") (pin "38") (pinfunction "PE7_38") (pintype "bidirectional"))
    )
    (net (code "115") (name "unconnected-(U1A-PE8-Pad39)") (class "Default")
      (node (ref "U1") (pin "39") (pinfunction "PE8_39") (pintype "bidirectional"))
    )
    (net (code "116") (name "unconnected-(U1A-PE9-Pad40)") (class "Default")
      (node (ref "U1") (pin "40") (pinfunction "PE9_40") (pintype "bidirectional"))
    )
    (net (code "117") (name "unconnected-(U1A-PE10-Pad41)") (class "Default")
      (node (ref "U1") (pin "41") (pinfunction "PE10_41") (pintype "bidirectional"))
    )
    (net (code "118") (name "unconnected-(U1A-PE11-Pad42)") (class "Default")
      (node (ref "U1") (pin "42") (pinfunction "PE11_42") (pintype "bidirectional"))
    )
    (net (code "119") (name "unconnected-(U1A-PE12-Pad43)") (class "Default")
      (node (ref "U1") (pin "43") (pinfunction "PE12_43") (pintype "bidirectional"))
    )
    (net (code "120") (name "unconnected-(U1A-PE13-Pad44)") (class "Default")
      (node (ref "U1") (pin "44") (pinfunction "PE13_44") (pintype "bidirectional"))
    )
    (net (code "121") (name "unconnected-(U1A-PE15-Pad46)") (class "Default")
      (node (ref "U1") (pin "46") (pinfunction "PE15_46") (pintype "bidirectional"))
    )
    (net (code "122") (name "unconnected-(U3-ADC{slash}TOUT-Pad2)") (class "Default")
      (node (ref "U3") (pin "2") (pinfunction "ADC/TOUT_2") (pintype "passive"))
    )
    (net (code "123") (name "unconnected-(U3-GPIO2{slash}TXD1-Pad11)") (class "Default")
      (node (ref "U3") (pin "11") (pinfunction "GPIO2/TXD1_11") (pintype "passive+no_connect"))
    )
    (net (code "124") (name "unconnected-(U3-GPIO4-Pad13)") (class "Default")
      (node (ref "U3") (pin "13") (pinfunction "GPIO4_13") (pintype "passive+no_connect"))
    )
    (net (code "125") (name "unconnected-(U3-GPIO5-Pad14)") (class "Default")
      (node (ref "U3") (pin "14") (pinfunction "GPIO5_14") (pintype "passive+no_connect"))
    )
    (net (code "126") (name "unconnected-(U3-GPIO12{slash}HSPIQ-Pad6)") (class "Default")
      (node (ref "U3") (pin "6") (pinfunction "GPIO12/HSPIQ_6") (pintype "passive+no_connect"))
    )
    (net (code "127") (name "unconnected-(U3-GPIO13{slash}HSPID{slash}CTS0{slash}RXD2-Pad7)") (class "Default")
      (node (ref "U3") (pin "7") (pinfunction "GPIO13/HSPID/CTS0/RXD2_7") (pintype "passive+no_connect"))
    )
    (net (code "128") (name "unconnected-(U3-GPIO14{slash}HSPICLK-Pad5)") (class "Default")
      (node (ref "U3") (pin "5") (pinfunction "GPIO14/HSPICLK_5") (pintype "passive+no_connect"))
    )
    (net (code "129") (name "unconnected-(U3-GPIO16{slash}~{WAKE}-Pad4)") (class "Default")
      (node (ref "U3") (pin "4") (pinfunction "GPIO16/~{WAKE}_4") (pintype "passive"))
    )
    (net (code "130") (name "unconnected-(U4-GPIO0{slash}RXOKLED-Pad15)") (class "Default")
      (node (ref "U4") (pin "15") (pinfunction "GPIO0/RXOKLED_15") (pintype "bidirectional"))
    )
    (net (code "131") (name "unconnected-(U4-GPIO1{slash}SFDLED-Pad14)") (class "Default")
      (node (ref "U4") (pin "14") (pinfunction "GPIO1/SFDLED_14") (pintype "bidirectional"))
    )
    (net (code "132") (name "unconnected-(U4-GPIO2{slash}RXLED-Pad13)") (class "Default")
      (node (ref "U4") (pin "13") (pinfunction "GPIO2/RXLED_13") (pintype "bidirectional"))
    )
    (net (code "133") (name "unconnected-(U4-GPIO3{slash}TXLED-Pad12)") (class "Default")
      (node (ref "U4") (pin "12") (pinfunction "GPIO3/TXLED_12") (pintype "bidirectional"))
    )
    (net (code "134") (name "unconnected-(U4-GPIO4-Pad11)") (class "Default")
      (node (ref "U4") (pin "11") (pinfunction "GPIO4_11") (pintype "bidirectional"))
    )
    (net (code "135") (name "unconnected-(U4-GPIO5{slash}SPIPOL-Pad10)") (class "Default")
      (node (ref "U4") (pin "10") (pinfunction "GPIO5/SPIPOL_10") (pintype "bidirectional"))
    )
    (net (code "136") (name "unconnected-(U4-GPIO6{slash}SPIPHA-Pad9)") (class "Default")
      (node (ref "U4") (pin "9") (pinfunction "GPIO6/SPIPHA_9") (pintype "bidirectional"))
    )
    (net (code "137") (name "unconnected-(U4-GPIO7-Pad4)") (class "Default")
      (node (ref "U4") (pin "4") (pinfunction "GPIO7_4") (pintype "bidirectional"))
    )
    (net (code "138") (name "unconnected-(U5-DI01-Pad6)") (class "Default")
      (node (ref "U5") (pin "6") (pinfunction "DI01_6") (pintype "bidirectional"))
    )
    (net (code "139") (name "unconnected-(U5-DI02-Pad7)") (class "Default")
      (node (ref "U5") (pin "7") (pinfunction "DI02_7") (pintype "bidirectional"))
    )
    (net (code "140") (name "unconnected-(U5-DI03-Pad8)") (class "Default")
      (node (ref "U5") (pin "8") (pinfunction "DI03_8") (pintype "bidirectional"))
    )
    (net (code "141") (name "unconnected-(U5-DI04-Pad10)") (class "Default")
      (node (ref "U5") (pin "10") (pinfunction "DI04_10") (pintype "bidirectional"))
    )
    (net (code "142") (name "unconnected-(U5-DI05-Pad11)") (class "Default")
      (node (ref "U5") (pin "11") (pinfunction "DI05_11") (pintype "bidirectional"))
    )
  )
)
